# 1-Schematic_Industrial_Environment_Quali.net
KiCad netlist of a schematic drawn in EasyEDA
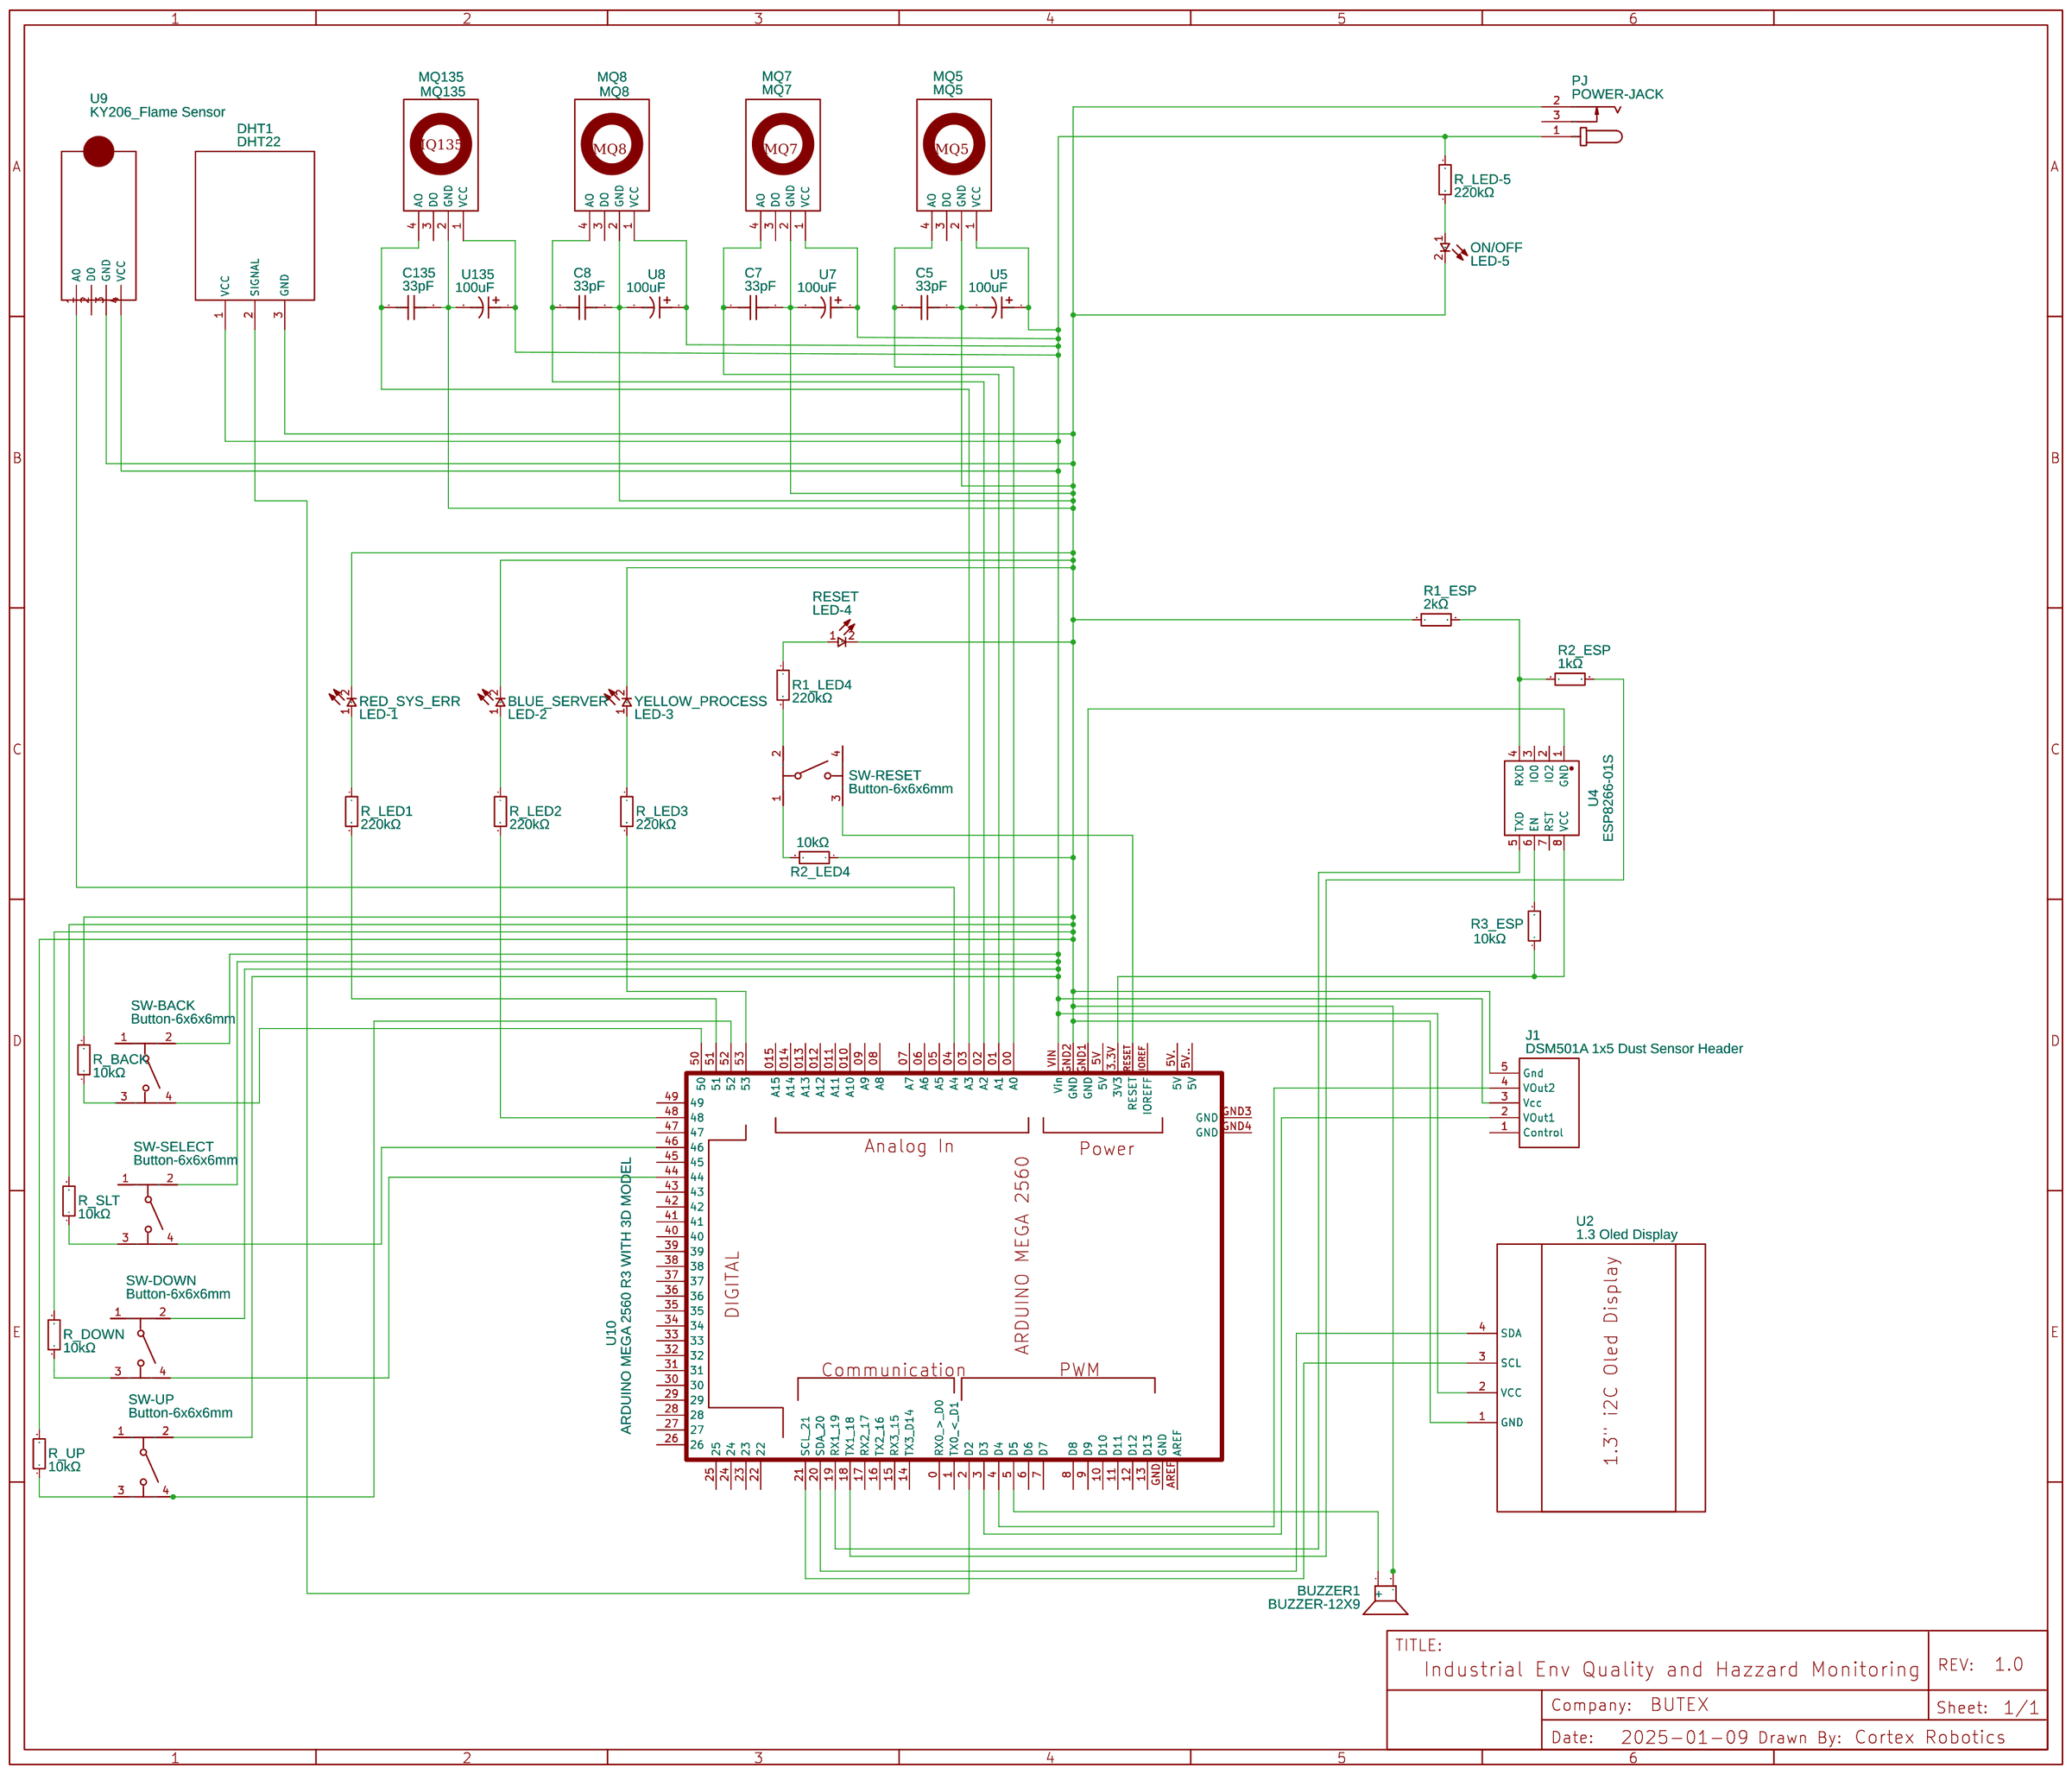
[diagram p0: schematic sheet]

(export (version "E")
  (design (tool "Eeschema 10.0.6"))
  (components
    (comp (ref "BLUE_SERVER")
      (value "LED-2")
      (fields (field (name "Manufacturer Part") "5600") (field (name "Manufacturer") "VccLite"))
      (libsource (lib "") (part "LED-1 COPY COPY_2"))
    )
    (comp (ref "BUZZER1")
      (value "BUZZER-12X9")
      (fields (field (name "Manufacturer Part") "buzzer-12X9"))
      (libsource (lib "") (part "BUZZER-12X9"))
    )
    (comp (ref "C5")
      (value "33pF")
      (fields
        (field (name "Manufacturer Part") "CCBCapacitor 100PF100v")
        (field (name "Manufacturer") "ReliaPro")
      )
      (libsource (lib "") (part "CCBCapacitor 100PF100v"))
    )
    (comp (ref "C7")
      (value "33pF")
      (fields
        (field (name "Manufacturer Part") "CCBCapacitor 100PF100v")
        (field (name "Manufacturer") "ReliaPro")
      )
      (libsource (lib "") (part "CCBCapacitor 100PF100v"))
    )
    (comp (ref "C8")
      (value "33pF")
      (fields
        (field (name "Manufacturer Part") "CCBCapacitor 100PF100v")
        (field (name "Manufacturer") "ReliaPro")
      )
      (libsource (lib "") (part "CCBCapacitor 100PF100v"))
    )
    (comp (ref "C135")
      (value "33pF")
      (fields
        (field (name "Manufacturer Part") "CCBCapacitor 100PF100v")
        (field (name "Manufacturer") "ReliaPro")
      )
      (libsource (lib "") (part "CCBCapacitor 100PF100v"))
    )
    (comp (ref "DHT1")
      (value "DHT22")
      (fields (field (name "Manufacturer Part") "Jared"))
      (libsource (lib "") (part "DHT22"))
    )
    (comp (ref "J1")
      (value "DSM501A 1x5 Dust Sensor Header")
      (libsource (lib "") (part "DSM501A 1x5 Dust Sensor Header"))
    )
    (comp (ref "MQ5") (value "MQ5") (libsource (lib "") (part "MQ_1")))
    (comp (ref "MQ7") (value "MQ7") (libsource (lib "") (part "MQ_3")))
    (comp (ref "MQ8") (value "MQ8") (libsource (lib "") (part "MQ")))
    (comp (ref "MQ135") (value "MQ135") (libsource (lib "") (part "MQ_2")))
    (comp (ref "ON/OFF")
      (value "LED-5")
      (fields (field (name "Manufacturer Part") "5600") (field (name "Manufacturer") "VccLite"))
      (libsource (lib "") (part "LED-1 COPY COPY_4"))
    )
    (comp (ref "PJ")
      (value "POWER-JACK")
      (fields (field (name "Manufacturer") "索峰"))
      (libsource (lib "") (part "POWER-JACK"))
    )
    (comp (ref "R1_ESP")
      (value "2kΩ")
      (fields
        (field (name "Manufacturer Part") "EWWR0001J20R0T9")
        (field (name "Manufacturer") "ResistorToday")
      )
      (libsource (lib "") (part "RESISTOR NORMAL_1"))
    )
    (comp (ref "R1_LED4")
      (value "220kΩ")
      (fields
        (field (name "Manufacturer Part") "EWWR0001J20R0T9")
        (field (name "Manufacturer") "ResistorToday")
      )
      (libsource (lib "") (part "RESISTOR NORMAL"))
    )
    (comp (ref "R2_ESP")
      (value "1kΩ")
      (fields
        (field (name "Manufacturer Part") "EWWR0001J20R0T9")
        (field (name "Manufacturer") "ResistorToday")
      )
      (libsource (lib "") (part "RESISTOR NORMAL_4"))
    )
    (comp (ref "R2_LED4")
      (value "10kΩ")
      (fields
        (field (name "Manufacturer Part") "EWWR0001J20R0T9")
        (field (name "Manufacturer") "ResistorToday")
      )
      (libsource (lib "") (part "RESISTOR NORMAL_10"))
    )
    (comp (ref "R3_ESP")
      (value "10kΩ")
      (fields
        (field (name "Manufacturer Part") "EWWR0001J20R0T9")
        (field (name "Manufacturer") "ResistorToday")
      )
      (libsource (lib "") (part "RESISTOR NORMAL_5"))
    )
    (comp (ref "RED_SYS_ERR")
      (value "LED-1")
      (fields (field (name "Manufacturer Part") "5600") (field (name "Manufacturer") "VccLite"))
      (libsource (lib "") (part "LED-1 COPY COPY_1"))
    )
    (comp (ref "RESET")
      (value "LED-4")
      (fields (field (name "Manufacturer Part") "5600") (field (name "Manufacturer") "VccLite"))
      (libsource (lib "") (part "LED-1 COPY COPY_3"))
    )
    (comp (ref "R_BACK")
      (value "10kΩ")
      (fields
        (field (name "Manufacturer Part") "EWWR0001J20R0T9")
        (field (name "Manufacturer") "ResistorToday")
      )
      (libsource (lib "") (part "RESISTOR NORMAL_9"))
    )
    (comp (ref "R_DOWN")
      (value "10kΩ")
      (fields
        (field (name "Manufacturer Part") "EWWR0001J20R0T9")
        (field (name "Manufacturer") "ResistorToday")
      )
      (libsource (lib "") (part "RESISTOR NORMAL_7"))
    )
    (comp (ref "R_LED-5")
      (value "220kΩ")
      (fields
        (field (name "Manufacturer Part") "EWWR0001J20R0T9")
        (field (name "Manufacturer") "ResistorToday")
      )
      (libsource (lib "") (part "RESISTOR NORMAL_6"))
    )
    (comp (ref "R_LED1")
      (value "220kΩ")
      (fields
        (field (name "Manufacturer Part") "EWWR0001J20R0T9")
        (field (name "Manufacturer") "ResistorToday")
      )
      (libsource (lib "") (part "RESISTOR NORMAL_2"))
    )
    (comp (ref "R_LED2")
      (value "220kΩ")
      (fields
        (field (name "Manufacturer Part") "EWWR0001J20R0T9")
        (field (name "Manufacturer") "ResistorToday")
      )
      (libsource (lib "") (part "RESISTOR NORMAL_2"))
    )
    (comp (ref "R_LED3")
      (value "220kΩ")
      (fields
        (field (name "Manufacturer Part") "EWWR0001J20R0T9")
        (field (name "Manufacturer") "ResistorToday")
      )
      (libsource (lib "") (part "RESISTOR NORMAL_2"))
    )
    (comp (ref "R_SLT")
      (value "10kΩ")
      (fields
        (field (name "Manufacturer Part") "EWWR0001J20R0T9")
        (field (name "Manufacturer") "ResistorToday")
      )
      (libsource (lib "") (part "RESISTOR NORMAL_3"))
    )
    (comp (ref "R_UP")
      (value "10kΩ")
      (fields
        (field (name "Manufacturer Part") "EWWR0001J20R0T9")
        (field (name "Manufacturer") "ResistorToday")
      )
      (libsource (lib "") (part "RESISTOR NORMAL_8"))
    )
    (comp (ref "SW-BACK")
      (value "Button-6x6x6mm")
      (fields
        (field (name "Manufacturer Part") "Switch,6*6*6Plastic head,260G, 0.25mm,Straight line")
        (field (name "Manufacturer") "BBJ")
      )
      (libsource (lib "") (part "Button-6x6x6mm_4"))
    )
    (comp (ref "SW-DOWN")
      (value "Button-6x6x6mm")
      (fields
        (field (name "Manufacturer Part") "Switch,6*6*6Plastic head,260G, 0.25mm,Straight line")
        (field (name "Manufacturer") "BBJ")
      )
      (libsource (lib "") (part "Button-6x6x6mm_3"))
    )
    (comp (ref "SW-RESET")
      (value "Button-6x6x6mm")
      (fields
        (field (name "Manufacturer Part") "Switch,6*6*6Plastic head,260G, 0.25mm,Straight line")
        (field (name "Manufacturer") "BBJ")
      )
      (libsource (lib "") (part "Button-6x6x6mm_1"))
    )
    (comp (ref "SW-SELECT")
      (value "Button-6x6x6mm")
      (fields
        (field (name "Manufacturer Part") "Switch,6*6*6Plastic head,260G, 0.25mm,Straight line")
        (field (name "Manufacturer") "BBJ")
      )
      (libsource (lib "") (part "Button-6x6x6mm_2"))
    )
    (comp (ref "SW-UP")
      (value "Button-6x6x6mm")
      (fields
        (field (name "Manufacturer Part") "Switch,6*6*6Plastic head,260G, 0.25mm,Straight line")
        (field (name "Manufacturer") "BBJ")
      )
      (libsource (lib "") (part "Button-6x6x6mm"))
    )
    (comp (ref "U2") (value "1.3 Oled Display") (libsource (lib "") (part "1.3 Oled Display")))
    (comp (ref "U4") (value "ESP8266-01S") (libsource (lib "") (part "ESP8266-01S")))
    (comp (ref "U5")
      (value "100uF")
      (fields
        (field (name "Manufacturer Part") "KNE2100UF10V149EC0013")
        (field (name "Manufacturer") "KNSCHA(科尼盛)")
      )
      (libsource (lib "") (part "KNE2100UF10V149EC0013"))
    )
    (comp (ref "U7")
      (value "100uF")
      (fields
        (field (name "Manufacturer Part") "KNE2100UF10V149EC0013")
        (field (name "Manufacturer") "KNSCHA(科尼盛)")
      )
      (libsource (lib "") (part "KNE2100UF10V149EC0013"))
    )
    (comp (ref "U8")
      (value "100uF")
      (fields
        (field (name "Manufacturer Part") "KNE2100UF10V149EC0013")
        (field (name "Manufacturer") "KNSCHA(科尼盛)")
      )
      (libsource (lib "") (part "KNE2100UF10V149EC0013"))
    )
    (comp (ref "U9") (value "KY206_Flame Sensor") (libsource (lib "") (part "Flame Sensor")))
    (comp (ref "U10")
      (value "ARDUINO MEGA 2560 R3 WITH 3D MODEL")
      (fields (field (name "Manufacturer") "matan"))
      (libsource (lib "") (part "ARDUINO MEGA 2560 R3 WITH 3D MODEL"))
    )
    (comp (ref "U135")
      (value "100uF")
      (fields
        (field (name "Manufacturer Part") "KNE2100UF10V149EC0013")
        (field (name "Manufacturer") "KNSCHA(科尼盛)")
      )
      (libsource (lib "") (part "KNE2100UF10V149EC0013"))
    )
    (comp (ref "YELLOW_PROCESS")
      (value "LED-3")
      (fields (field (name "Manufacturer Part") "5600") (field (name "Manufacturer") "VccLite"))
      (libsource (lib "") (part "LED-1 COPY COPY"))
    )
  )
  (nets
    (net (code "1") (name "Net-(BLUE_SERVER-A)") (class "Default")
      (node (ref "BLUE_SERVER") (pin "1") (pinfunction "A_1") (pintype "input"))
      (node (ref "R_LED2") (pin "1") (pinfunction "1_1") (pintype "unspecified"))
    )
    (net (code "2") (name "Net-(BLUE_SERVER-K)") (class "Default")
      (node (ref "BLUE_SERVER") (pin "2") (pinfunction "K_2") (pintype "input"))
      (node (ref "BUZZER1") (pin "2") (pinfunction "2_2") (pintype "unspecified"))
      (node (ref "C135") (pin "2") (pinfunction "2_2") (pintype "unspecified"))
      (node (ref "C5") (pin "2") (pinfunction "2_2") (pintype "unspecified"))
      (node (ref "C7") (pin "2") (pinfunction "2_2") (pintype "unspecified"))
      (node (ref "C8") (pin "2") (pinfunction "2_2") (pintype "unspecified"))
      (node (ref "DHT1") (pin "3") (pinfunction "GND_3") (pintype "unspecified"))
      (node (ref "J1") (pin "5") (pinfunction "Gnd_5") (pintype "unspecified"))
      (node (ref "MQ135") (pin "2") (pinfunction "GND_2") (pintype "unspecified"))
      (node (ref "MQ5") (pin "2") (pinfunction "GND_2") (pintype "unspecified"))
      (node (ref "MQ7") (pin "2") (pinfunction "GND_2") (pintype "unspecified"))
      (node (ref "MQ8") (pin "2") (pinfunction "GND_2") (pintype "unspecified"))
      (node (ref "ON/OFF") (pin "2") (pinfunction "K_2") (pintype "input"))
      (node (ref "PJ") (pin "2") (pinfunction "2_2") (pintype "unspecified"))
      (node (ref "R1_ESP") (pin "1") (pinfunction "1_1") (pintype "unspecified"))
      (node (ref "R2_LED4") (pin "1") (pinfunction "1_1") (pintype "unspecified"))
      (node (ref "RED_SYS_ERR") (pin "2") (pinfunction "K_2") (pintype "input"))
      (node (ref "RESET") (pin "2") (pinfunction "K_2") (pintype "input"))
      (node (ref "R_BACK") (pin "2") (pinfunction "2_2") (pintype "unspecified"))
      (node (ref "R_DOWN") (pin "2") (pinfunction "2_2") (pintype "unspecified"))
      (node (ref "R_SLT") (pin "2") (pinfunction "2_2") (pintype "unspecified"))
      (node (ref "R_UP") (pin "2") (pinfunction "2_2") (pintype "unspecified"))
      (node (ref "U10") (pin "GND2") (pinfunction "GND_GND2") (pintype "unspecified"))
      (node (ref "U135") (pin "2") (pinfunction "2_2") (pintype "input"))
      (node (ref "U2") (pin "1") (pinfunction "GND_1") (pintype "unspecified"))
      (node (ref "U5") (pin "2") (pinfunction "2_2") (pintype "input"))
      (node (ref "U7") (pin "2") (pinfunction "2_2") (pintype "input"))
      (node (ref "U8") (pin "2") (pinfunction "2_2") (pintype "input"))
      (node (ref "U9") (pin "3") (pinfunction "GND_3") (pintype "unspecified"))
      (node (ref "YELLOW_PROCESS") (pin "2") (pinfunction "K_2") (pintype "input"))
    )
    (net (code "3") (name "Net-(BUZZER1-+)") (class "Default")
      (node (ref "BUZZER1") (pin "1") (pinfunction "+_1") (pintype "unspecified"))
      (node (ref "U10") (pin "5") (pinfunction "D5_5") (pintype "unspecified"))
    )
    (net (code "4") (name "Net-(DHT1-SIGNAL)") (class "Default")
      (node (ref "DHT1") (pin "2") (pinfunction "SIGNAL_2") (pintype "unspecified"))
      (node (ref "U10") (pin "2") (pinfunction "D2_2") (pintype "unspecified"))
    )
    (net (code "5") (name "Net-(DHT1-VCC)") (class "Default")
      (node (ref "DHT1") (pin "1") (pinfunction "VCC_1") (pintype "unspecified"))
      (node (ref "J1") (pin "3") (pinfunction "Vcc_3") (pintype "unspecified"))
      (node (ref "MQ135") (pin "1") (pinfunction "VCC_1") (pintype "unspecified"))
      (node (ref "MQ5") (pin "1") (pinfunction "VCC_1") (pintype "unspecified"))
      (node (ref "MQ7") (pin "1") (pinfunction "VCC_1") (pintype "unspecified"))
      (node (ref "MQ8") (pin "1") (pinfunction "VCC_1") (pintype "unspecified"))
      (node (ref "PJ") (pin "1") (pinfunction "1_1") (pintype "unspecified"))
      (node (ref "R_LED-5") (pin "1") (pinfunction "1_1") (pintype "unspecified"))
      (node (ref "SW-BACK") (pin "2") (pinfunction "2_2") (pintype "unspecified"))
      (node (ref "SW-DOWN") (pin "2") (pinfunction "2_2") (pintype "unspecified"))
      (node (ref "SW-SELECT") (pin "2") (pinfunction "2_2") (pintype "unspecified"))
      (node (ref "SW-UP") (pin "2") (pinfunction "2_2") (pintype "unspecified"))
      (node (ref "U10") (pin "VIN") (pinfunction "Vin_VIN") (pintype "unspecified"))
      (node (ref "U135") (pin "1") (pinfunction "1_1") (pintype "input"))
      (node (ref "U2") (pin "2") (pinfunction "VCC_2") (pintype "unspecified"))
      (node (ref "U5") (pin "1") (pinfunction "1_1") (pintype "input"))
      (node (ref "U7") (pin "1") (pinfunction "1_1") (pintype "input"))
      (node (ref "U8") (pin "1") (pinfunction "1_1") (pintype "input"))
      (node (ref "U9") (pin "4") (pinfunction "VCC_4") (pintype "unspecified"))
    )
    (net (code "6") (name "Net-(J1-VOut1)") (class "Default")
      (node (ref "J1") (pin "2") (pinfunction "VOut1_2") (pintype "unspecified"))
      (node (ref "U10") (pin "3") (pinfunction "D3_3") (pintype "unspecified"))
    )
    (net (code "7") (name "Net-(J1-VOut2)") (class "Default")
      (node (ref "J1") (pin "4") (pinfunction "VOut2_4") (pintype "unspecified"))
      (node (ref "U10") (pin "4") (pinfunction "D4_4") (pintype "unspecified"))
    )
    (net (code "8") (name "Net-(MQ5-AO)") (class "Default")
      (node (ref "C5") (pin "1") (pinfunction "1_1") (pintype "unspecified"))
      (node (ref "MQ5") (pin "4") (pinfunction "AO_4") (pintype "unspecified"))
      (node (ref "U10") (pin "00") (pinfunction "A0_00") (pintype "unspecified"))
    )
    (net (code "9") (name "Net-(MQ7-AO)") (class "Default")
      (node (ref "C7") (pin "1") (pinfunction "1_1") (pintype "unspecified"))
      (node (ref "MQ7") (pin "4") (pinfunction "AO_4") (pintype "unspecified"))
      (node (ref "U10") (pin "01") (pinfunction "A1_01") (pintype "unspecified"))
    )
    (net (code "10") (name "Net-(MQ8-AO)") (class "Default")
      (node (ref "C8") (pin "1") (pinfunction "1_1") (pintype "unspecified"))
      (node (ref "MQ8") (pin "4") (pinfunction "AO_4") (pintype "unspecified"))
      (node (ref "U10") (pin "02") (pinfunction "A2_02") (pintype "unspecified"))
    )
    (net (code "11") (name "Net-(MQ135-AO)") (class "Default")
      (node (ref "C135") (pin "1") (pinfunction "1_1") (pintype "unspecified"))
      (node (ref "MQ135") (pin "4") (pinfunction "AO_4") (pintype "unspecified"))
      (node (ref "U10") (pin "03") (pinfunction "A3_03") (pintype "unspecified"))
    )
    (net (code "12") (name "Net-(ON/OFF-A)") (class "Default")
      (node (ref "ON/OFF") (pin "1") (pinfunction "A_1") (pintype "input"))
      (node (ref "R_LED-5") (pin "2") (pinfunction "2_2") (pintype "unspecified"))
    )
    (net (code "13") (name "Net-(R1_LED4-Pad2)") (class "Default")
      (node (ref "R1_LED4") (pin "2") (pinfunction "2_2") (pintype "unspecified"))
      (node (ref "SW-RESET") (pin "2") (pinfunction "2_2") (pintype "unspecified"))
    )
    (net (code "14") (name "Net-(R2_LED4-Pad2)") (class "Default")
      (node (ref "R2_LED4") (pin "2") (pinfunction "2_2") (pintype "unspecified"))
      (node (ref "SW-RESET") (pin "1") (pinfunction "1_1") (pintype "unspecified"))
    )
    (net (code "15") (name "Net-(RED_SYS_ERR-A)") (class "Default")
      (node (ref "RED_SYS_ERR") (pin "1") (pinfunction "A_1") (pintype "input"))
      (node (ref "R_LED1") (pin "1") (pinfunction "1_1") (pintype "unspecified"))
    )
    (net (code "16") (name "Net-(RESET-A)") (class "Default")
      (node (ref "R1_LED4") (pin "1") (pinfunction "1_1") (pintype "unspecified"))
      (node (ref "RESET") (pin "1") (pinfunction "A_1") (pintype "input"))
    )
    (net (code "17") (name "Net-(R_BACK-Pad1)") (class "Default")
      (node (ref "R_BACK") (pin "1") (pinfunction "1_1") (pintype "unspecified"))
      (node (ref "SW-BACK") (pin "3") (pinfunction "3_3") (pintype "unspecified"))
    )
    (net (code "18") (name "Net-(R_DOWN-Pad1)") (class "Default")
      (node (ref "R_DOWN") (pin "1") (pinfunction "1_1") (pintype "unspecified"))
      (node (ref "SW-DOWN") (pin "3") (pinfunction "3_3") (pintype "unspecified"))
    )
    (net (code "19") (name "Net-(R_LED1-Pad2)") (class "Default")
      (node (ref "R_LED1") (pin "2") (pinfunction "2_2") (pintype "unspecified"))
      (node (ref "U10") (pin "51") (pinfunction "51_51") (pintype "unspecified"))
    )
    (net (code "20") (name "Net-(R_LED2-Pad2)") (class "Default")
      (node (ref "R_LED2") (pin "2") (pinfunction "2_2") (pintype "unspecified"))
      (node (ref "U10") (pin "48") (pinfunction "48_48") (pintype "unspecified"))
    )
    (net (code "21") (name "Net-(R_LED3-Pad2)") (class "Default")
      (node (ref "R_LED3") (pin "2") (pinfunction "2_2") (pintype "unspecified"))
      (node (ref "U10") (pin "53") (pinfunction "53_53") (pintype "unspecified"))
    )
    (net (code "22") (name "Net-(R_SLT-Pad1)") (class "Default")
      (node (ref "R_SLT") (pin "1") (pinfunction "1_1") (pintype "unspecified"))
      (node (ref "SW-SELECT") (pin "3") (pinfunction "3_3") (pintype "unspecified"))
    )
    (net (code "23") (name "Net-(R_UP-Pad1)") (class "Default")
      (node (ref "R_UP") (pin "1") (pinfunction "1_1") (pintype "unspecified"))
      (node (ref "SW-UP") (pin "3") (pinfunction "3_3") (pintype "unspecified"))
    )
    (net (code "24") (name "Net-(SW-BACK-Pad4)") (class "Default")
      (node (ref "SW-BACK") (pin "4") (pinfunction "4_4") (pintype "unspecified"))
      (node (ref "U10") (pin "50") (pinfunction "50_50") (pintype "unspecified"))
    )
    (net (code "25") (name "Net-(SW-DOWN-Pad4)") (class "Default")
      (node (ref "SW-DOWN") (pin "4") (pinfunction "4_4") (pintype "unspecified"))
      (node (ref "U10") (pin "44") (pinfunction "44_44") (pintype "unspecified"))
    )
    (net (code "26") (name "Net-(SW-RESET-Pad3)") (class "Default")
      (node (ref "SW-RESET") (pin "3") (pinfunction "3_3") (pintype "unspecified"))
      (node (ref "U10") (pin "RESET") (pinfunction "RESET_RESET") (pintype "unspecified"))
    )
    (net (code "27") (name "Net-(SW-SELECT-Pad4)") (class "Default")
      (node (ref "SW-SELECT") (pin "4") (pinfunction "4_4") (pintype "unspecified"))
      (node (ref "U10") (pin "46") (pinfunction "46_46") (pintype "unspecified"))
    )
    (net (code "28") (name "Net-(SW-UP-Pad4)") (class "Default")
      (node (ref "SW-UP") (pin "4") (pinfunction "4_4") (pintype "unspecified"))
      (node (ref "U10") (pin "52") (pinfunction "52_52") (pintype "unspecified"))
    )
    (net (code "29") (name "Net-(U4-EN)") (class "Default")
      (node (ref "R3_ESP") (pin "2") (pinfunction "2_2") (pintype "unspecified"))
      (node (ref "U4") (pin "6") (pinfunction "EN_6") (pintype "unspecified"))
    )
    (net (code "30") (name "Net-(U4-GND)") (class "Default")
      (node (ref "U10") (pin "GND1") (pinfunction "GND_GND1") (pintype "unspecified"))
      (node (ref "U4") (pin "1") (pinfunction "GND_1") (pintype "unspecified"))
    )
    (net (code "31") (name "Net-(U4-RXD)") (class "Default")
      (node (ref "R1_ESP") (pin "2") (pinfunction "2_2") (pintype "unspecified"))
      (node (ref "R2_ESP") (pin "1") (pinfunction "1_1") (pintype "unspecified"))
      (node (ref "U4") (pin "4") (pinfunction "RXD_4") (pintype "unspecified"))
    )
    (net (code "32") (name "Net-(U10-3V3)") (class "Default")
      (node (ref "R3_ESP") (pin "1") (pinfunction "1_1") (pintype "unspecified"))
      (node (ref "U10") (pin "3.3V") (pinfunction "3V3_3.3V") (pintype "unspecified"))
      (node (ref "U4") (pin "8") (pinfunction "VCC_8") (pintype "unspecified"))
    )
    (net (code "33") (name "Net-(U10-A4)") (class "Default")
      (node (ref "U10") (pin "04") (pinfunction "A4_04") (pintype "unspecified"))
      (node (ref "U9") (pin "1") (pinfunction "A0_1") (pintype "unspecified"))
    )
    (net (code "34") (name "Net-(U10-RX1_19)") (class "Default")
      (node (ref "U10") (pin "19") (pinfunction "RX1_19_19") (pintype "unspecified"))
      (node (ref "U4") (pin "5") (pinfunction "TXD_5") (pintype "unspecified"))
    )
    (net (code "35") (name "Net-(U10-SCL_21)") (class "Default")
      (node (ref "U10") (pin "21") (pinfunction "SCL_21_21") (pintype "unspecified"))
      (node (ref "U2") (pin "3") (pinfunction "SCL_3") (pintype "unspecified"))
    )
    (net (code "36") (name "Net-(U10-SDA_20)") (class "Default")
      (node (ref "U10") (pin "20") (pinfunction "SDA_20_20") (pintype "unspecified"))
      (node (ref "U2") (pin "4") (pinfunction "SDA_4") (pintype "unspecified"))
    )
    (net (code "37") (name "Net-(U10-TX1_18)") (class "Default")
      (node (ref "R2_ESP") (pin "2") (pinfunction "2_2") (pintype "unspecified"))
      (node (ref "U10") (pin "18") (pinfunction "TX1_18_18") (pintype "unspecified"))
    )
    (net (code "38") (name "Net-(YELLOW_PROCESS-A)") (class "Default")
      (node (ref "R_LED3") (pin "1") (pinfunction "1_1") (pintype "unspecified"))
      (node (ref "YELLOW_PROCESS") (pin "1") (pinfunction "A_1") (pintype "input"))
    )
    (net (code "39") (name "unconnected-(J1-Control-Pad1)") (class "Default")
      (node (ref "J1") (pin "1") (pinfunction "Control_1") (pintype "unspecified"))
    )
    (net (code "40") (name "unconnected-(MQ5-DO-Pad3)") (class "Default")
      (node (ref "MQ5") (pin "3") (pinfunction "DO_3") (pintype "unspecified"))
    )
    (net (code "41") (name "unconnected-(MQ7-DO-Pad3)") (class "Default")
      (node (ref "MQ7") (pin "3") (pinfunction "DO_3") (pintype "unspecified"))
    )
    (net (code "42") (name "unconnected-(MQ8-DO-Pad3)") (class "Default")
      (node (ref "MQ8") (pin "3") (pinfunction "DO_3") (pintype "unspecified"))
    )
    (net (code "43") (name "unconnected-(MQ135-DO-Pad3)") (class "Default")
      (node (ref "MQ135") (pin "3") (pinfunction "DO_3") (pintype "unspecified"))
    )
    (net (code "44") (name "unconnected-(PJ-Pad3)") (class "Default")
      (node (ref "PJ") (pin "3") (pinfunction "3_3") (pintype "unspecified"))
    )
    (net (code "45") (name "unconnected-(SW-BACK-Pad1)") (class "Default")
      (node (ref "SW-BACK") (pin "1") (pinfunction "1_1") (pintype "unspecified"))
    )
    (net (code "46") (name "unconnected-(SW-DOWN-Pad1)") (class "Default")
      (node (ref "SW-DOWN") (pin "1") (pinfunction "1_1") (pintype "unspecified"))
    )
    (net (code "47") (name "unconnected-(SW-RESET-Pad4)") (class "Default")
      (node (ref "SW-RESET") (pin "4") (pinfunction "4_4") (pintype "unspecified"))
    )
    (net (code "48") (name "unconnected-(SW-SELECT-Pad1)") (class "Default")
      (node (ref "SW-SELECT") (pin "1") (pinfunction "1_1") (pintype "unspecified"))
    )
    (net (code "49") (name "unconnected-(SW-UP-Pad1)") (class "Default")
      (node (ref "SW-UP") (pin "1") (pinfunction "1_1") (pintype "unspecified"))
    )
    (net (code "50") (name "unconnected-(U4-IO0-Pad3)") (class "Default")
      (node (ref "U4") (pin "3") (pinfunction "IO0_3") (pintype "unspecified"))
    )
    (net (code "51") (name "unconnected-(U4-IO2-Pad2)") (class "Default")
      (node (ref "U4") (pin "2") (pinfunction "IO2_2") (pintype "unspecified"))
    )
    (net (code "52") (name "unconnected-(U4-RST-Pad7)") (class "Default")
      (node (ref "U4") (pin "7") (pinfunction "RST_7") (pintype "unspecified"))
    )
    (net (code "53") (name "unconnected-(U9-D0-Pad2)") (class "Default")
      (node (ref "U9") (pin "2") (pinfunction "D0_2") (pintype "unspecified"))
    )
    (net (code "54") (name "unconnected-(U10-5V-Pad5V.)") (class "Default")
      (node (ref "U10") (pin "5V.") (pinfunction "5V_5V.") (pintype "unspecified"))
    )
    (net (code "55") (name "unconnected-(U10-5V-Pad5V..)") (class "Default")
      (node (ref "U10") (pin "5V..") (pinfunction "5V_5V..") (pintype "unspecified"))
    )
    (net (code "56") (name "unconnected-(U10-A5-Pad05)") (class "Default")
      (node (ref "U10") (pin "05") (pinfunction "A5_05") (pintype "unspecified"))
    )
    (net (code "57") (name "unconnected-(U10-A6-Pad06)") (class "Default")
      (node (ref "U10") (pin "06") (pinfunction "A6_06") (pintype "unspecified"))
    )
    (net (code "58") (name "unconnected-(U10-A7-Pad07)") (class "Default")
      (node (ref "U10") (pin "07") (pinfunction "A7_07") (pintype "unspecified"))
    )
    (net (code "59") (name "unconnected-(U10-A8-Pad08)") (class "Default")
      (node (ref "U10") (pin "08") (pinfunction "A8_08") (pintype "unspecified"))
    )
    (net (code "60") (name "unconnected-(U10-A9-Pad09)") (class "Default")
      (node (ref "U10") (pin "09") (pinfunction "A9_09") (pintype "unspecified"))
    )
    (net (code "61") (name "unconnected-(U10-A10-Pad010)") (class "Default")
      (node (ref "U10") (pin "010") (pinfunction "A10_010") (pintype "unspecified"))
    )
    (net (code "62") (name "unconnected-(U10-A11-Pad011)") (class "Default")
      (node (ref "U10") (pin "011") (pinfunction "A11_011") (pintype "unspecified"))
    )
    (net (code "63") (name "unconnected-(U10-A12-Pad012)") (class "Default")
      (node (ref "U10") (pin "012") (pinfunction "A12_012") (pintype "unspecified"))
    )
    (net (code "64") (name "unconnected-(U10-A13-Pad013)") (class "Default")
      (node (ref "U10") (pin "013") (pinfunction "A13_013") (pintype "unspecified"))
    )
    (net (code "65") (name "unconnected-(U10-A14-Pad014)") (class "Default")
      (node (ref "U10") (pin "014") (pinfunction "A14_014") (pintype "unspecified"))
    )
    (net (code "66") (name "unconnected-(U10-A15-Pad015)") (class "Default")
      (node (ref "U10") (pin "015") (pinfunction "A15_015") (pintype "unspecified"))
    )
    (net (code "67") (name "unconnected-(U10-D6-Pad6)") (class "Default")
      (node (ref "U10") (pin "6") (pinfunction "D6_6") (pintype "unspecified"))
    )
    (net (code "68") (name "unconnected-(U10-D7-Pad7)") (class "Default")
      (node (ref "U10") (pin "7") (pinfunction "D7_7") (pintype "unspecified"))
    )
    (net (code "69") (name "unconnected-(U10-D8-Pad8)") (class "Default")
      (node (ref "U10") (pin "8") (pinfunction "D8_8") (pintype "unspecified"))
    )
    (net (code "70") (name "unconnected-(U10-D9-Pad9)") (class "Default")
      (node (ref "U10") (pin "9") (pinfunction "D9_9") (pintype "unspecified"))
    )
    (net (code "71") (name "unconnected-(U10-D10-Pad10)") (class "Default")
      (node (ref "U10") (pin "10") (pinfunction "D10_10") (pintype "unspecified"))
    )
    (net (code "72") (name "unconnected-(U10-D11-Pad11)") (class "Default")
      (node (ref "U10") (pin "11") (pinfunction "D11_11") (pintype "unspecified"))
    )
    (net (code "73") (name "unconnected-(U10-D12-Pad12)") (class "Default")
      (node (ref "U10") (pin "12") (pinfunction "D12_12") (pintype "unspecified"))
    )
    (net (code "74") (name "unconnected-(U10-D13-Pad13)") (class "Default")
      (node (ref "U10") (pin "13") (pinfunction "D13_13") (pintype "unspecified"))
    )
    (net (code "75") (name "unconnected-(U10-GND-PadGND3)") (class "Default")
      (node (ref "U10") (pin "GND3") (pinfunction "GND_GND3") (pintype "unspecified"))
    )
    (net (code "76") (name "unconnected-(U10-GND-PadGND4)") (class "Default")
      (node (ref "U10") (pin "GND4") (pinfunction "GND_GND4") (pintype "unspecified"))
    )
    (net (code "77") (name "unconnected-(U10-IOREFF-PadIOREF)") (class "Default")
      (node (ref "U10") (pin "IOREF") (pinfunction "IOREFF_IOREF") (pintype "unspecified"))
    )
    (net (code "78") (name "unconnected-(U10-Pad5V)") (class "Default")
      (node (ref "U10") (pin "5V") (pinfunction "5V_5V") (pintype "unspecified"))
    )
    (net (code "79") (name "unconnected-(U10-Pad22)") (class "Default")
      (node (ref "U10") (pin "22") (pinfunction "22_22") (pintype "unspecified"))
    )
    (net (code "80") (name "unconnected-(U10-Pad23)") (class "Default")
      (node (ref "U10") (pin "23") (pinfunction "23_23") (pintype "unspecified"))
    )
    (net (code "81") (name "unconnected-(U10-Pad24)") (class "Default")
      (node (ref "U10") (pin "24") (pinfunction "24_24") (pintype "unspecified"))
    )
    (net (code "82") (name "unconnected-(U10-Pad25)") (class "Default")
      (node (ref "U10") (pin "25") (pinfunction "25_25") (pintype "unspecified"))
    )
    (net (code "83") (name "unconnected-(U10-Pad26)") (class "Default")
      (node (ref "U10") (pin "26") (pinfunction "26_26") (pintype "unspecified"))
    )
    (net (code "84") (name "unconnected-(U10-Pad27)") (class "Default")
      (node (ref "U10") (pin "27") (pinfunction "27_27") (pintype "unspecified"))
    )
    (net (code "85") (name "unconnected-(U10-Pad28)") (class "Default")
      (node (ref "U10") (pin "28") (pinfunction "28_28") (pintype "unspecified"))
    )
    (net (code "86") (name "unconnected-(U10-Pad29)") (class "Default")
      (node (ref "U10") (pin "29") (pinfunction "29_29") (pintype "unspecified"))
    )
    (net (code "87") (name "unconnected-(U10-Pad30)") (class "Default")
      (node (ref "U10") (pin "30") (pinfunction "30_30") (pintype "unspecified"))
    )
    (net (code "88") (name "unconnected-(U10-Pad31)") (class "Default")
      (node (ref "U10") (pin "31") (pinfunction "31_31") (pintype "unspecified"))
    )
    (net (code "89") (name "unconnected-(U10-Pad32)") (class "Default")
      (node (ref "U10") (pin "32") (pinfunction "32_32") (pintype "unspecified"))
    )
    (net (code "90") (name "unconnected-(U10-Pad33)") (class "Default")
      (node (ref "U10") (pin "33") (pinfunction "33_33") (pintype "unspecified"))
    )
    (net (code "91") (name "unconnected-(U10-Pad34)") (class "Default")
      (node (ref "U10") (pin "34") (pinfunction "34_34") (pintype "unspecified"))
    )
    (net (code "92") (name "unconnected-(U10-Pad35)") (class "Default")
      (node (ref "U10") (pin "35") (pinfunction "35_35") (pintype "unspecified"))
    )
    (net (code "93") (name "unconnected-(U10-Pad36)") (class "Default")
      (node (ref "U10") (pin "36") (pinfunction "36_36") (pintype "unspecified"))
    )
    (net (code "94") (name "unconnected-(U10-Pad37)") (class "Default")
      (node (ref "U10") (pin "37") (pinfunction "37_37") (pintype "unspecified"))
    )
    (net (code "95") (name "unconnected-(U10-Pad38)") (class "Default")
      (node (ref "U10") (pin "38") (pinfunction "38_38") (pintype "unspecified"))
    )
    (net (code "96") (name "unconnected-(U10-Pad39)") (class "Default")
      (node (ref "U10") (pin "39") (pinfunction "39_39") (pintype "unspecified"))
    )
    (net (code "97") (name "unconnected-(U10-Pad40)") (class "Default")
      (node (ref "U10") (pin "40") (pinfunction "40_40") (pintype "unspecified"))
    )
    (net (code "98") (name "unconnected-(U10-Pad41)") (class "Default")
      (node (ref "U10") (pin "41") (pinfunction "41_41") (pintype "unspecified"))
    )
    (net (code "99") (name "unconnected-(U10-Pad42)") (class "Default")
      (node (ref "U10") (pin "42") (pinfunction "42_42") (pintype "unspecified"))
    )
    (net (code "100") (name "unconnected-(U10-Pad43)") (class "Default")
      (node (ref "U10") (pin "43") (pinfunction "43_43") (pintype "unspecified"))
    )
    (net (code "101") (name "unconnected-(U10-Pad45)") (class "Default")
      (node (ref "U10") (pin "45") (pinfunction "45_45") (pintype "unspecified"))
    )
    (net (code "102") (name "unconnected-(U10-Pad47)") (class "Default")
      (node (ref "U10") (pin "47") (pinfunction "47_47") (pintype "unspecified"))
    )
    (net (code "103") (name "unconnected-(U10-Pad49)") (class "Default")
      (node (ref "U10") (pin "49") (pinfunction "49_49") (pintype "unspecified"))
    )
    (net (code "104") (name "unconnected-(U10-PadAREF)") (class "Default")
      (node (ref "U10") (pin "AREF") (pinfunction "AREF_AREF") (pintype "unspecified"))
    )
    (net (code "105") (name "unconnected-(U10-PadGND)") (class "Default")
      (node (ref "U10") (pin "GND") (pinfunction "GND_GND") (pintype "unspecified"))
    )
    (net (code "106") (name "unconnected-(U10-RX0_>_D0-Pad0)") (class "Default")
      (node (ref "U10") (pin "0") (pinfunction "RX0_>_D0_0") (pintype "unspecified"))
    )
    (net (code "107") (name "unconnected-(U10-RX2_17-Pad17)") (class "Default")
      (node (ref "U10") (pin "17") (pinfunction "RX2_17_17") (pintype "unspecified"))
    )
    (net (code "108") (name "unconnected-(U10-RX3_15-Pad15)") (class "Default")
      (node (ref "U10") (pin "15") (pinfunction "RX3_15_15") (pintype "unspecified"))
    )
    (net (code "109") (name "unconnected-(U10-TX0_<_D1-Pad1)") (class "Default")
      (node (ref "U10") (pin "1") (pinfunction "TX0_<_D1_1") (pintype "unspecified"))
    )
    (net (code "110") (name "unconnected-(U10-TX2_16-Pad16)") (class "Default")
      (node (ref "U10") (pin "16") (pinfunction "TX2_16_16") (pintype "unspecified"))
    )
    (net (code "111") (name "unconnected-(U10-TX3_D14-Pad14)") (class "Default")
      (node (ref "U10") (pin "14") (pinfunction "TX3_D14_14") (pintype "unspecified"))
    )
  )
)
